# RFID_Reader_v1_0.net
KiCad netlist of a schematic drawn in EAGLE
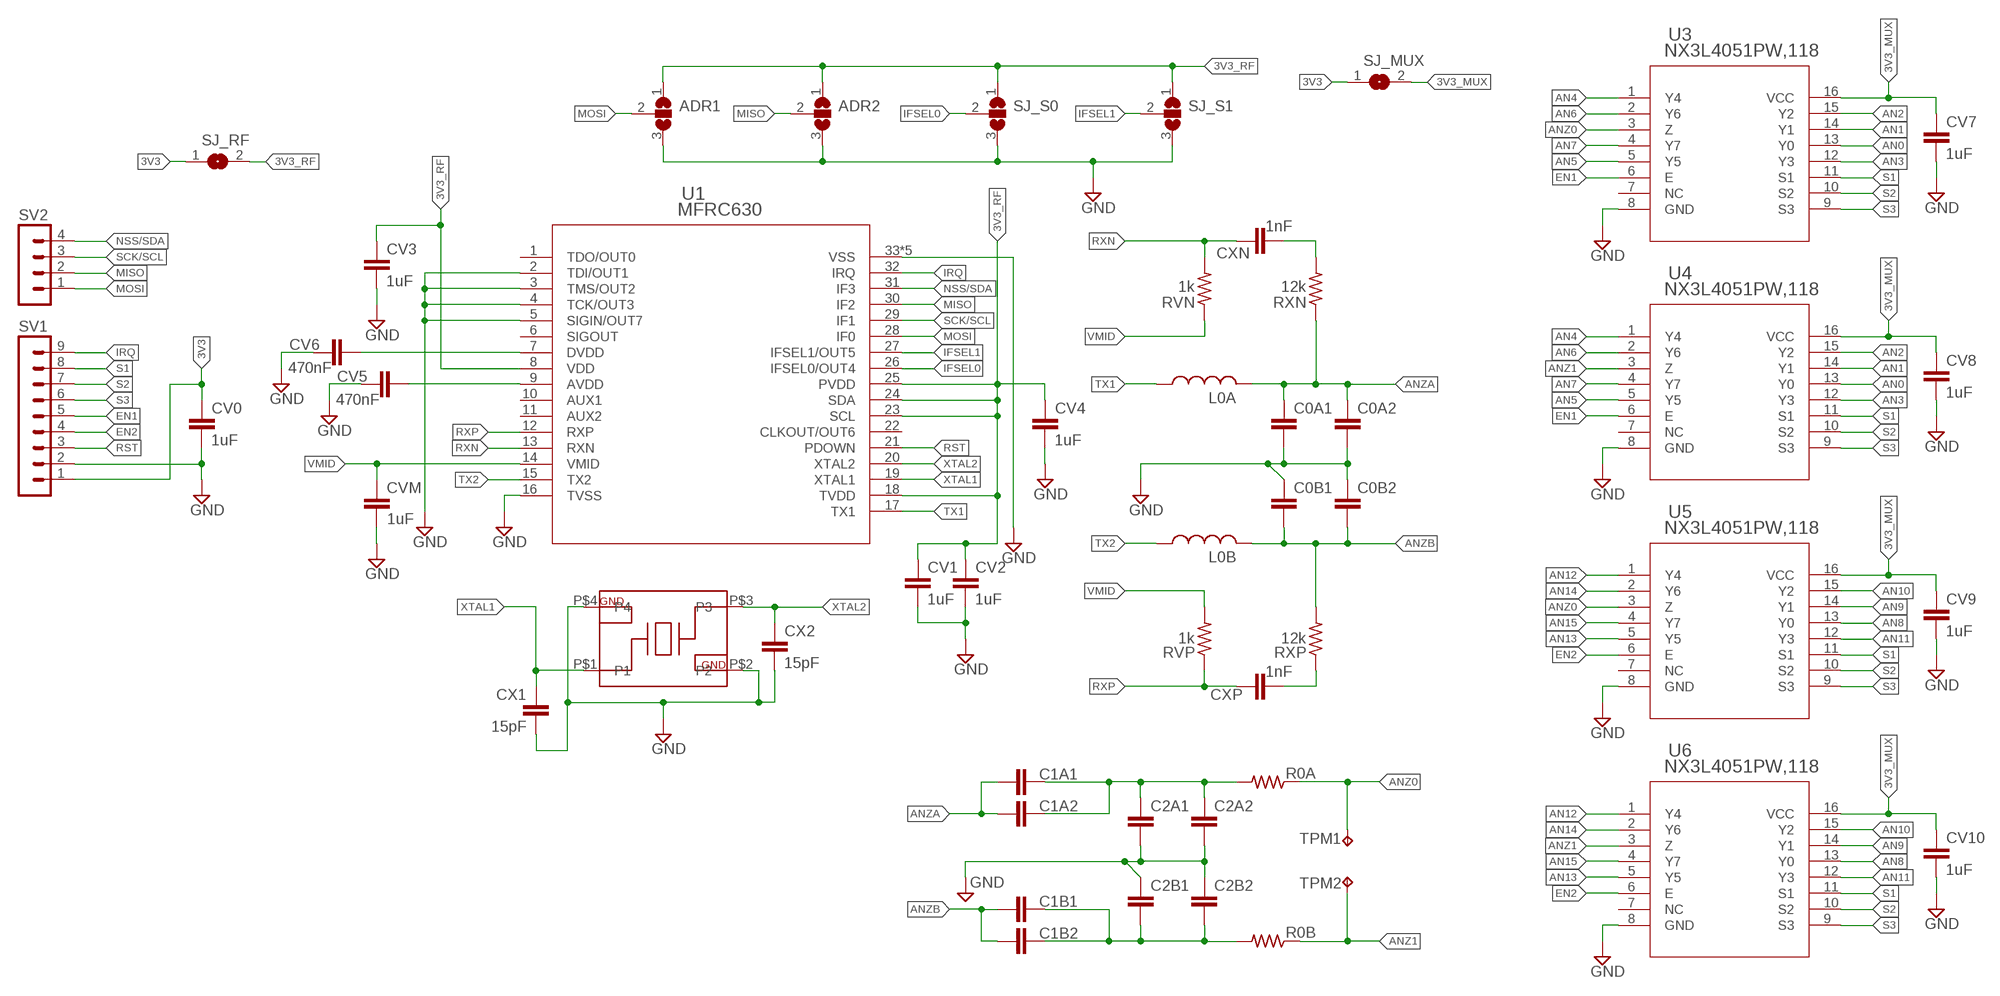
[diagram p0: schematic, sheet 1]

(export (version "E")
  (design (tool "Eeschema 10.0.6"))
  (components
    (comp (ref "ADR1")
      (value "SJ2W")
      (footprint "eagle-import:SJ_2")
      (libsource (lib "eagle-import") (part "SJ2W"))
    )
    (comp (ref "ADR2")
      (value "SJ2W")
      (footprint "eagle-import:SJ_2")
      (libsource (lib "eagle-import") (part "SJ2W"))
    )
    (comp (ref "C0A1")
      (value "C-EUC0805")
      (footprint "eagle-import:C0805")
      (libsource (lib "eagle-import") (part "C-EUC0805"))
    )
    (comp (ref "C0A2")
      (value "C-EUC0805")
      (footprint "eagle-import:C0805")
      (libsource (lib "eagle-import") (part "C-EUC0805"))
    )
    (comp (ref "C0B1")
      (value "C-EUC0805")
      (footprint "eagle-import:C0805")
      (libsource (lib "eagle-import") (part "C-EUC0805"))
    )
    (comp (ref "C0B2")
      (value "C-EUC0805")
      (footprint "eagle-import:C0805")
      (libsource (lib "eagle-import") (part "C-EUC0805"))
    )
    (comp (ref "C1A1")
      (value "C-EUC0805")
      (footprint "eagle-import:C0805")
      (libsource (lib "eagle-import") (part "C-EUC0805"))
    )
    (comp (ref "C1A2")
      (value "C-EUC0805")
      (footprint "eagle-import:C0805")
      (libsource (lib "eagle-import") (part "C-EUC0805"))
    )
    (comp (ref "C1B1")
      (value "C-EUC0805")
      (footprint "eagle-import:C0805")
      (libsource (lib "eagle-import") (part "C-EUC0805"))
    )
    (comp (ref "C1B2")
      (value "C-EUC0805")
      (footprint "eagle-import:C0805")
      (libsource (lib "eagle-import") (part "C-EUC0805"))
    )
    (comp (ref "C2A1")
      (value "C-EUC0805")
      (footprint "eagle-import:C0805")
      (libsource (lib "eagle-import") (part "C-EUC0805"))
    )
    (comp (ref "C2A2")
      (value "C-EUC0805")
      (footprint "eagle-import:C0805")
      (libsource (lib "eagle-import") (part "C-EUC0805"))
    )
    (comp (ref "C2B1")
      (value "C-EUC0805")
      (footprint "eagle-import:C0805")
      (libsource (lib "eagle-import") (part "C-EUC0805"))
    )
    (comp (ref "C2B2")
      (value "C-EUC0805")
      (footprint "eagle-import:C0805")
      (libsource (lib "eagle-import") (part "C-EUC0805"))
    )
    (comp (ref "CV0")
      (value "1uF")
      (footprint "eagle-import:C0402")
      (libsource (lib "eagle-import") (part "C-EUC0402"))
    )
    (comp (ref "CV1")
      (value "1uF")
      (footprint "eagle-import:C0402")
      (libsource (lib "eagle-import") (part "C-EUC0402"))
    )
    (comp (ref "CV2")
      (value "1uF")
      (footprint "eagle-import:C0402")
      (libsource (lib "eagle-import") (part "C-EUC0402"))
    )
    (comp (ref "CV3")
      (value "1uF")
      (footprint "eagle-import:C0402")
      (libsource (lib "eagle-import") (part "C-EUC0402"))
    )
    (comp (ref "CV4")
      (value "1uF")
      (footprint "eagle-import:C0402")
      (libsource (lib "eagle-import") (part "C-EUC0402"))
    )
    (comp (ref "CV5")
      (value "470nF")
      (footprint "eagle-import:C0402")
      (libsource (lib "eagle-import") (part "C-EUC0402"))
    )
    (comp (ref "CV6")
      (value "470nF")
      (footprint "eagle-import:C0402")
      (libsource (lib "eagle-import") (part "C-EUC0402"))
    )
    (comp (ref "CV7")
      (value "1uF")
      (footprint "eagle-import:C0402")
      (libsource (lib "eagle-import") (part "C-EUC0402"))
    )
    (comp (ref "CV8")
      (value "1uF")
      (footprint "eagle-import:C0402")
      (libsource (lib "eagle-import") (part "C-EUC0402"))
    )
    (comp (ref "CV9")
      (value "1uF")
      (footprint "eagle-import:C0402")
      (libsource (lib "eagle-import") (part "C-EUC0402"))
    )
    (comp (ref "CV10")
      (value "1uF")
      (footprint "eagle-import:C0402")
      (libsource (lib "eagle-import") (part "C-EUC0402"))
    )
    (comp (ref "CVM")
      (value "1uF")
      (footprint "eagle-import:C0402")
      (libsource (lib "eagle-import") (part "C-EUC0402"))
    )
    (comp (ref "CX1")
      (value "15pF")
      (footprint "eagle-import:C0402")
      (libsource (lib "eagle-import") (part "C-EUC0402"))
    )
    (comp (ref "CX2")
      (value "15pF")
      (footprint "eagle-import:C0402")
      (libsource (lib "eagle-import") (part "C-EUC0402"))
    )
    (comp (ref "CXN")
      (value "1nF")
      (footprint "eagle-import:C0805")
      (libsource (lib "eagle-import") (part "C-EUC0805"))
    )
    (comp (ref "CXP")
      (value "1nF")
      (footprint "eagle-import:C0805")
      (libsource (lib "eagle-import") (part "C-EUC0805"))
    )
    (comp (ref "L0A")
      (value "L0806")
      (footprint "eagle-import:L0806")
      (libsource (lib "eagle-import") (part "L0806"))
    )
    (comp (ref "L0B")
      (value "L0806")
      (footprint "eagle-import:L0806")
      (libsource (lib "eagle-import") (part "L0806"))
    )
    (comp (ref "R0A")
      (value "R-US_R0805")
      (footprint "eagle-import:R0805")
      (libsource (lib "eagle-import") (part "R-US_R0805"))
    )
    (comp (ref "R0B")
      (value "R-US_R0805")
      (footprint "eagle-import:R0805")
      (libsource (lib "eagle-import") (part "R-US_R0805"))
    )
    (comp (ref "RVN")
      (value "1k")
      (footprint "eagle-import:R0805")
      (libsource (lib "eagle-import") (part "R-US_R0805"))
    )
    (comp (ref "RVP")
      (value "1k")
      (footprint "eagle-import:R0805")
      (libsource (lib "eagle-import") (part "R-US_R0805"))
    )
    (comp (ref "RXN")
      (value "12k")
      (footprint "eagle-import:R0805")
      (libsource (lib "eagle-import") (part "R-US_R0805"))
    )
    (comp (ref "RXP")
      (value "12k")
      (footprint "eagle-import:R0805")
      (libsource (lib "eagle-import") (part "R-US_R0805"))
    )
    (comp (ref "SJ_MUX")
      (value "SJ")
      (footprint "eagle-import:SJ")
      (libsource (lib "eagle-import") (part "SJ"))
    )
    (comp (ref "SJ_RF")
      (value "SJ")
      (footprint "eagle-import:SJ")
      (libsource (lib "eagle-import") (part "SJ"))
    )
    (comp (ref "SJ_S0")
      (value "SJ2W")
      (footprint "eagle-import:SJ_2")
      (libsource (lib "eagle-import") (part "SJ2W"))
    )
    (comp (ref "SJ_S1")
      (value "SJ2W")
      (footprint "eagle-import:SJ_2")
      (libsource (lib "eagle-import") (part "SJ2W"))
    )
    (comp (ref "SV1")
      (value "MA09-1")
      (footprint "eagle-import:MA09-1")
      (libsource (lib "eagle-import") (part "MA09-1"))
    )
    (comp (ref "SV2")
      (value "MA04-1")
      (footprint "eagle-import:MA04-1")
      (libsource (lib "eagle-import") (part "MA04-1"))
    )
    (comp (ref "TPM1")
      (value "TPTP10R")
      (footprint "eagle-import:TP10R")
      (libsource (lib "eagle-import") (part "TPTP10R"))
    )
    (comp (ref "TPM2")
      (value "TPTP10R")
      (footprint "eagle-import:TP10R")
      (libsource (lib "eagle-import") (part "TPTP10R"))
    )
    (comp (ref "U1")
      (value "MFRC630")
      (footprint "eagle-import:HVQFN32_SOT617-1_NXP-M")
      (fields
        (field (name "MANUFACTURER_PART_NUMBER") "MFRC63002HN,118")
        (field (name "COPYRIGHT") "Copyright (C) 2024 Ultra Librarian. All rights reserved.")
      )
      (libsource (lib "eagle-import") (part "MFRC63002HN,118HVQFN32_SOT617-1_NXP-M"))
    )
    (comp (ref "U2")
      (value "E3SB27")
      (footprint "eagle-import:DFN320X250X75-4N")
      (libsource (lib "eagle-import") (part "E3SB27E0X000VEE3SB27E0X000VE"))
    )
    (comp (ref "U3")
      (value "NX3L4051PW,118")
      (footprint "eagle-import:TSSOP16_NXP-M")
      (fields (field (name "COPYRIGHT") "Copyright (C) 2024 Ultra Librarian. All rights reserved."))
      (libsource (lib "eagle-import") (part "NX3L4051PW,118TSSOP16_NXP-M"))
    )
    (comp (ref "U4")
      (value "NX3L4051PW,118")
      (footprint "eagle-import:TSSOP16_NXP-M")
      (fields (field (name "COPYRIGHT") "Copyright (C) 2024 Ultra Librarian. All rights reserved."))
      (libsource (lib "eagle-import") (part "NX3L4051PW,118TSSOP16_NXP-M"))
    )
    (comp (ref "U5")
      (value "NX3L4051PW,118")
      (footprint "eagle-import:TSSOP16_NXP-M")
      (fields (field (name "COPYRIGHT") "Copyright (C) 2024 Ultra Librarian. All rights reserved."))
      (libsource (lib "eagle-import") (part "NX3L4051PW,118TSSOP16_NXP-M"))
    )
    (comp (ref "U6")
      (value "NX3L4051PW,118")
      (footprint "eagle-import:TSSOP16_NXP-M")
      (fields (field (name "COPYRIGHT") "Copyright (C) 2024 Ultra Librarian. All rights reserved."))
      (libsource (lib "eagle-import") (part "NX3L4051PW,118TSSOP16_NXP-M"))
    )
  )
  (nets
    (net (code "1") (name "3V3") (class "Default")
      (node (ref "CV0") (pin "1") (pinfunction "1_1") (pintype "passive"))
      (node (ref "SJ_MUX") (pin "1") (pinfunction "1_1") (pintype "passive"))
      (node (ref "SJ_RF") (pin "1") (pinfunction "1_1") (pintype "passive"))
      (node (ref "SV1") (pin "1") (pinfunction "1_1") (pintype "passive"))
    )
    (net (code "2") (name "3V3_MUX") (class "Default")
      (node (ref "CV10") (pin "1") (pinfunction "1_1") (pintype "passive"))
      (node (ref "CV7") (pin "1") (pinfunction "1_1") (pintype "passive"))
      (node (ref "CV8") (pin "1") (pinfunction "1_1") (pintype "passive"))
      (node (ref "CV9") (pin "1") (pinfunction "1_1") (pintype "passive"))
      (node (ref "SJ_MUX") (pin "2") (pinfunction "2_2") (pintype "passive"))
      (node (ref "U3") (pin "16") (pinfunction "VCC_16") (pintype "power_in"))
      (node (ref "U4") (pin "16") (pinfunction "VCC_16") (pintype "power_in"))
      (node (ref "U5") (pin "16") (pinfunction "VCC_16") (pintype "power_in"))
      (node (ref "U6") (pin "16") (pinfunction "VCC_16") (pintype "power_in"))
    )
    (net (code "3") (name "3V3_RF") (class "Default")
      (node (ref "ADR1") (pin "1") (pinfunction "1_1") (pintype "passive"))
      (node (ref "ADR2") (pin "1") (pinfunction "1_1") (pintype "passive"))
      (node (ref "CV1") (pin "1") (pinfunction "1_1") (pintype "passive"))
      (node (ref "CV2") (pin "1") (pinfunction "1_1") (pintype "passive"))
      (node (ref "CV3") (pin "1") (pinfunction "1_1") (pintype "passive"))
      (node (ref "CV4") (pin "1") (pinfunction "1_1") (pintype "passive"))
      (node (ref "SJ_RF") (pin "2") (pinfunction "2_2") (pintype "passive"))
      (node (ref "SJ_S0") (pin "1") (pinfunction "1_1") (pintype "passive"))
      (node (ref "SJ_S1") (pin "1") (pinfunction "1_1") (pintype "passive"))
      (node (ref "U1") (pin "18") (pinfunction "TVDD_18") (pintype "power_in"))
      (node (ref "U1") (pin "23") (pinfunction "SCL_23") (pintype "output"))
      (node (ref "U1") (pin "24") (pinfunction "SDA_24") (pintype "bidirectional"))
      (node (ref "U1") (pin "25") (pinfunction "PVDD_25") (pintype "power_in"))
      (node (ref "U1") (pin "8") (pinfunction "VDD_8") (pintype "power_in"))
    )
    (net (code "4") (name "AN0") (class "Default")
      (node (ref "U3") (pin "13") (pinfunction "Y0_13") (pintype "bidirectional"))
      (node (ref "U4") (pin "13") (pinfunction "Y0_13") (pintype "bidirectional"))
    )
    (net (code "5") (name "AN1") (class "Default")
      (node (ref "U3") (pin "14") (pinfunction "Y1_14") (pintype "bidirectional"))
      (node (ref "U4") (pin "14") (pinfunction "Y1_14") (pintype "bidirectional"))
    )
    (net (code "6") (name "AN2") (class "Default")
      (node (ref "U3") (pin "15") (pinfunction "Y2_15") (pintype "bidirectional"))
      (node (ref "U4") (pin "15") (pinfunction "Y2_15") (pintype "bidirectional"))
    )
    (net (code "7") (name "AN3") (class "Default")
      (node (ref "U3") (pin "12") (pinfunction "Y3_12") (pintype "bidirectional"))
      (node (ref "U4") (pin "12") (pinfunction "Y3_12") (pintype "bidirectional"))
    )
    (net (code "8") (name "AN4") (class "Default")
      (node (ref "U3") (pin "1") (pinfunction "Y4_1") (pintype "bidirectional"))
      (node (ref "U4") (pin "1") (pinfunction "Y4_1") (pintype "bidirectional"))
    )
    (net (code "9") (name "AN5") (class "Default")
      (node (ref "U3") (pin "5") (pinfunction "Y5_5") (pintype "bidirectional"))
      (node (ref "U4") (pin "5") (pinfunction "Y5_5") (pintype "bidirectional"))
    )
    (net (code "10") (name "AN6") (class "Default")
      (node (ref "U3") (pin "2") (pinfunction "Y6_2") (pintype "bidirectional"))
      (node (ref "U4") (pin "2") (pinfunction "Y6_2") (pintype "bidirectional"))
    )
    (net (code "11") (name "AN7") (class "Default")
      (node (ref "U3") (pin "4") (pinfunction "Y7_4") (pintype "bidirectional"))
      (node (ref "U4") (pin "4") (pinfunction "Y7_4") (pintype "bidirectional"))
    )
    (net (code "12") (name "AN8") (class "Default")
      (node (ref "U5") (pin "13") (pinfunction "Y0_13") (pintype "bidirectional"))
      (node (ref "U6") (pin "13") (pinfunction "Y0_13") (pintype "bidirectional"))
    )
    (net (code "13") (name "AN9") (class "Default")
      (node (ref "U5") (pin "14") (pinfunction "Y1_14") (pintype "bidirectional"))
      (node (ref "U6") (pin "14") (pinfunction "Y1_14") (pintype "bidirectional"))
    )
    (net (code "14") (name "AN10") (class "Default")
      (node (ref "U5") (pin "15") (pinfunction "Y2_15") (pintype "bidirectional"))
      (node (ref "U6") (pin "15") (pinfunction "Y2_15") (pintype "bidirectional"))
    )
    (net (code "15") (name "AN11") (class "Default")
      (node (ref "U5") (pin "12") (pinfunction "Y3_12") (pintype "bidirectional"))
      (node (ref "U6") (pin "12") (pinfunction "Y3_12") (pintype "bidirectional"))
    )
    (net (code "16") (name "AN12") (class "Default")
      (node (ref "U5") (pin "1") (pinfunction "Y4_1") (pintype "bidirectional"))
      (node (ref "U6") (pin "1") (pinfunction "Y4_1") (pintype "bidirectional"))
    )
    (net (code "17") (name "AN13") (class "Default")
      (node (ref "U5") (pin "5") (pinfunction "Y5_5") (pintype "bidirectional"))
      (node (ref "U6") (pin "5") (pinfunction "Y5_5") (pintype "bidirectional"))
    )
    (net (code "18") (name "AN14") (class "Default")
      (node (ref "U5") (pin "2") (pinfunction "Y6_2") (pintype "bidirectional"))
      (node (ref "U6") (pin "2") (pinfunction "Y6_2") (pintype "bidirectional"))
    )
    (net (code "19") (name "AN15") (class "Default")
      (node (ref "U5") (pin "4") (pinfunction "Y7_4") (pintype "bidirectional"))
      (node (ref "U6") (pin "4") (pinfunction "Y7_4") (pintype "bidirectional"))
    )
    (net (code "20") (name "ANZ0") (class "Default")
      (node (ref "R0A") (pin "1") (pinfunction "1_1") (pintype "passive"))
      (node (ref "TPM1") (pin "TP") (pinfunction "TP_TP") (pintype "input"))
      (node (ref "U3") (pin "3") (pinfunction "Z_3") (pintype "bidirectional"))
      (node (ref "U5") (pin "3") (pinfunction "Z_3") (pintype "bidirectional"))
    )
    (net (code "21") (name "ANZ1") (class "Default")
      (node (ref "R0B") (pin "1") (pinfunction "1_1") (pintype "passive"))
      (node (ref "TPM2") (pin "TP") (pinfunction "TP_TP") (pintype "input"))
      (node (ref "U4") (pin "3") (pinfunction "Z_3") (pintype "bidirectional"))
      (node (ref "U6") (pin "3") (pinfunction "Z_3") (pintype "bidirectional"))
    )
    (net (code "22") (name "ANZA") (class "Default")
      (node (ref "C0A1") (pin "1") (pinfunction "1_1") (pintype "passive"))
      (node (ref "C0A2") (pin "1") (pinfunction "1_1") (pintype "passive"))
      (node (ref "C1A1") (pin "2") (pinfunction "2_2") (pintype "passive"))
      (node (ref "C1A2") (pin "2") (pinfunction "2_2") (pintype "passive"))
      (node (ref "L0A") (pin "2") (pinfunction "2_2") (pintype "passive"))
      (node (ref "RXN") (pin "1") (pinfunction "1_1") (pintype "passive"))
    )
    (net (code "23") (name "ANZB") (class "Default")
      (node (ref "C0B1") (pin "2") (pinfunction "2_2") (pintype "passive"))
      (node (ref "C0B2") (pin "2") (pinfunction "2_2") (pintype "passive"))
      (node (ref "C1B1") (pin "2") (pinfunction "2_2") (pintype "passive"))
      (node (ref "C1B2") (pin "2") (pinfunction "2_2") (pintype "passive"))
      (node (ref "L0B") (pin "2") (pinfunction "2_2") (pintype "passive"))
      (node (ref "RXP") (pin "2") (pinfunction "2_2") (pintype "passive"))
    )
    (net (code "24") (name "EN1") (class "Default")
      (node (ref "SV1") (pin "5") (pinfunction "5_5") (pintype "passive"))
      (node (ref "U3") (pin "6") (pinfunction "E_6") (pintype "input"))
      (node (ref "U4") (pin "6") (pinfunction "E_6") (pintype "input"))
    )
    (net (code "25") (name "EN2") (class "Default")
      (node (ref "SV1") (pin "4") (pinfunction "4_4") (pintype "passive"))
      (node (ref "U5") (pin "6") (pinfunction "E_6") (pintype "input"))
      (node (ref "U6") (pin "6") (pinfunction "E_6") (pintype "input"))
    )
    (net (code "26") (name "GND") (class "Default")
      (node (ref "ADR1") (pin "3") (pinfunction "3_3") (pintype "passive"))
      (node (ref "ADR2") (pin "3") (pinfunction "3_3") (pintype "passive"))
      (node (ref "C0A1") (pin "2") (pinfunction "2_2") (pintype "passive"))
      (node (ref "C0A2") (pin "2") (pinfunction "2_2") (pintype "passive"))
      (node (ref "C0B1") (pin "1") (pinfunction "1_1") (pintype "passive"))
      (node (ref "C0B2") (pin "1") (pinfunction "1_1") (pintype "passive"))
      (node (ref "C2A1") (pin "2") (pinfunction "2_2") (pintype "passive"))
      (node (ref "C2A2") (pin "2") (pinfunction "2_2") (pintype "passive"))
      (node (ref "C2B1") (pin "1") (pinfunction "1_1") (pintype "passive"))
      (node (ref "C2B2") (pin "1") (pinfunction "1_1") (pintype "passive"))
      (node (ref "CV0") (pin "2") (pinfunction "2_2") (pintype "passive"))
      (node (ref "CV1") (pin "2") (pinfunction "2_2") (pintype "passive"))
      (node (ref "CV10") (pin "2") (pinfunction "2_2") (pintype "passive"))
      (node (ref "CV2") (pin "2") (pinfunction "2_2") (pintype "passive"))
      (node (ref "CV3") (pin "2") (pinfunction "2_2") (pintype "passive"))
      (node (ref "CV4") (pin "2") (pinfunction "2_2") (pintype "passive"))
      (node (ref "CV5") (pin "2") (pinfunction "2_2") (pintype "passive"))
      (node (ref "CV6") (pin "2") (pinfunction "2_2") (pintype "passive"))
      (node (ref "CV7") (pin "2") (pinfunction "2_2") (pintype "passive"))
      (node (ref "CV8") (pin "2") (pinfunction "2_2") (pintype "passive"))
      (node (ref "CV9") (pin "2") (pinfunction "2_2") (pintype "passive"))
      (node (ref "CVM") (pin "2") (pinfunction "2_2") (pintype "passive"))
      (node (ref "CX1") (pin "2") (pinfunction "2_2") (pintype "passive"))
      (node (ref "CX2") (pin "2") (pinfunction "2_2") (pintype "passive"))
      (node (ref "SJ_S0") (pin "3") (pinfunction "3_3") (pintype "passive"))
      (node (ref "SJ_S1") (pin "3") (pinfunction "3_3") (pintype "passive"))
      (node (ref "SV1") (pin "2") (pinfunction "2_2") (pintype "passive"))
      (node (ref "U1") (pin "16") (pinfunction "TVSS_16") (pintype "passive"))
      (node (ref "U1") (pin "2") (pinfunction "TDI/OUT1_2") (pintype "input"))
      (node (ref "U1") (pin "3") (pinfunction "TMS/OUT2_3") (pintype "input"))
      (node (ref "U1") (pin "33") (pinfunction "VSS_33") (pintype "passive"))
      (node (ref "U1") (pin "4") (pinfunction "TCK/OUT3_4") (pintype "input"))
      (node (ref "U1") (pin "5") (pinfunction "SIGIN/OUT7_5") (pintype "bidirectional"))
      (node (ref "U1") (pin "P$1") (pinfunction "VSS_P$1") (pintype "passive"))
      (node (ref "U1") (pin "P$2") (pinfunction "VSS_P$2") (pintype "passive"))
      (node (ref "U1") (pin "P$3") (pinfunction "VSS_P$3") (pintype "passive"))
      (node (ref "U1") (pin "P$4") (pinfunction "VSS_P$4") (pintype "passive"))
      (node (ref "U2") (pin "P$2") (pinfunction "P2_P$2") (pintype "input"))
      (node (ref "U2") (pin "P$4") (pinfunction "P4_P$4") (pintype "input"))
      (node (ref "U3") (pin "8") (pinfunction "GND_8") (pintype "passive"))
      (node (ref "U4") (pin "8") (pinfunction "GND_8") (pintype "passive"))
      (node (ref "U5") (pin "8") (pinfunction "GND_8") (pintype "passive"))
      (node (ref "U6") (pin "8") (pinfunction "GND_8") (pintype "passive"))
    )
    (net (code "27") (name "IFSEL0") (class "Default")
      (node (ref "SJ_S0") (pin "2") (pinfunction "2_2") (pintype "passive"))
      (node (ref "U1") (pin "26") (pinfunction "IFSEL0/OUT4_26") (pintype "input"))
    )
    (net (code "28") (name "IFSEL1") (class "Default")
      (node (ref "SJ_S1") (pin "2") (pinfunction "2_2") (pintype "passive"))
      (node (ref "U1") (pin "27") (pinfunction "IFSEL1/OUT5_27") (pintype "input"))
    )
    (net (code "29") (name "IRQ") (class "Default")
      (node (ref "SV1") (pin "9") (pinfunction "9_9") (pintype "passive"))
      (node (ref "U1") (pin "32") (pinfunction "IRQ_32") (pintype "output"))
    )
    (net (code "30") (name "MISO") (class "Default")
      (node (ref "ADR2") (pin "2") (pinfunction "2_2") (pintype "passive"))
      (node (ref "SV2") (pin "2") (pinfunction "2_2") (pintype "passive"))
      (node (ref "U1") (pin "30") (pinfunction "IF2_30") (pintype "bidirectional"))
    )
    (net (code "31") (name "MOSI") (class "Default")
      (node (ref "ADR1") (pin "2") (pinfunction "2_2") (pintype "passive"))
      (node (ref "SV2") (pin "1") (pinfunction "1_1") (pintype "passive"))
      (node (ref "U1") (pin "28") (pinfunction "IF0_28") (pintype "bidirectional"))
    )
    (net (code "32") (name "NSS{slash}SDA") (class "Default")
      (node (ref "SV2") (pin "4") (pinfunction "4_4") (pintype "passive"))
      (node (ref "U1") (pin "31") (pinfunction "IF3_31") (pintype "bidirectional"))
    )
    (net (code "33") (name "Net-(C1A1-Pad1)") (class "Default")
      (node (ref "C1A1") (pin "1") (pinfunction "1_1") (pintype "passive"))
      (node (ref "C1A2") (pin "1") (pinfunction "1_1") (pintype "passive"))
      (node (ref "C2A1") (pin "1") (pinfunction "1_1") (pintype "passive"))
      (node (ref "C2A2") (pin "1") (pinfunction "1_1") (pintype "passive"))
      (node (ref "R0A") (pin "2") (pinfunction "2_2") (pintype "passive"))
    )
    (net (code "34") (name "Net-(C1B1-Pad1)") (class "Default")
      (node (ref "C1B1") (pin "1") (pinfunction "1_1") (pintype "passive"))
      (node (ref "C1B2") (pin "1") (pinfunction "1_1") (pintype "passive"))
      (node (ref "C2B1") (pin "2") (pinfunction "2_2") (pintype "passive"))
      (node (ref "C2B2") (pin "2") (pinfunction "2_2") (pintype "passive"))
      (node (ref "R0B") (pin "2") (pinfunction "2_2") (pintype "passive"))
    )
    (net (code "35") (name "Net-(CXN-Pad2)") (class "Default")
      (node (ref "CXN") (pin "2") (pinfunction "2_2") (pintype "passive"))
      (node (ref "RXN") (pin "2") (pinfunction "2_2") (pintype "passive"))
    )
    (net (code "36") (name "Net-(CXP-Pad2)") (class "Default")
      (node (ref "CXP") (pin "2") (pinfunction "2_2") (pintype "passive"))
      (node (ref "RXP") (pin "1") (pinfunction "1_1") (pintype "passive"))
    )
    (net (code "37") (name "Net-(U1-AVDD)") (class "Default")
      (node (ref "CV5") (pin "1") (pinfunction "1_1") (pintype "passive"))
      (node (ref "U1") (pin "9") (pinfunction "AVDD_9") (pintype "power_in"))
    )
    (net (code "38") (name "Net-(U1-DVDD)") (class "Default")
      (node (ref "CV6") (pin "1") (pinfunction "1_1") (pintype "passive"))
      (node (ref "U1") (pin "7") (pinfunction "DVDD_7") (pintype "power_in"))
    )
    (net (code "39") (name "RST") (class "Default")
      (node (ref "SV1") (pin "3") (pinfunction "3_3") (pintype "passive"))
      (node (ref "U1") (pin "21") (pinfunction "PDOWN_21") (pintype "input"))
    )
    (net (code "40") (name "RXN") (class "Default")
      (node (ref "CXN") (pin "1") (pinfunction "1_1") (pintype "passive"))
      (node (ref "RVN") (pin "2") (pinfunction "2_2") (pintype "passive"))
      (node (ref "U1") (pin "13") (pinfunction "RXN_13") (pintype "input"))
    )
    (net (code "41") (name "RXP") (class "Default")
      (node (ref "CXP") (pin "1") (pinfunction "1_1") (pintype "passive"))
      (node (ref "RVP") (pin "1") (pinfunction "1_1") (pintype "passive"))
      (node (ref "U1") (pin "12") (pinfunction "RXP_12") (pintype "input"))
    )
    (net (code "42") (name "S1") (class "Default")
      (node (ref "SV1") (pin "8") (pinfunction "8_8") (pintype "passive"))
      (node (ref "U3") (pin "11") (pinfunction "S1_11") (pintype "input"))
      (node (ref "U4") (pin "11") (pinfunction "S1_11") (pintype "input"))
      (node (ref "U5") (pin "11") (pinfunction "S1_11") (pintype "input"))
      (node (ref "U6") (pin "11") (pinfunction "S1_11") (pintype "input"))
    )
    (net (code "43") (name "S2") (class "Default")
      (node (ref "SV1") (pin "7") (pinfunction "7_7") (pintype "passive"))
      (node (ref "U3") (pin "10") (pinfunction "S2_10") (pintype "input"))
      (node (ref "U4") (pin "10") (pinfunction "S2_10") (pintype "input"))
      (node (ref "U5") (pin "10") (pinfunction "S2_10") (pintype "input"))
      (node (ref "U6") (pin "10") (pinfunction "S2_10") (pintype "input"))
    )
    (net (code "44") (name "S3") (class "Default")
      (node (ref "SV1") (pin "6") (pinfunction "6_6") (pintype "passive"))
      (node (ref "U3") (pin "9") (pinfunction "S3_9") (pintype "input"))
      (node (ref "U4") (pin "9") (pinfunction "S3_9") (pintype "input"))
      (node (ref "U5") (pin "9") (pinfunction "S3_9") (pintype "input"))
      (node (ref "U6") (pin "9") (pinfunction "S3_9") (pintype "input"))
    )
    (net (code "45") (name "SCK{slash}SCL") (class "Default")
      (node (ref "SV2") (pin "3") (pinfunction "3_3") (pintype "passive"))
      (node (ref "U1") (pin "29") (pinfunction "IF1_29") (pintype "bidirectional"))
    )
    (net (code "46") (name "TX1") (class "Default")
      (node (ref "L0A") (pin "1") (pinfunction "1_1") (pintype "passive"))
      (node (ref "U1") (pin "17") (pinfunction "TX1_17") (pintype "output"))
    )
    (net (code "47") (name "TX2") (class "Default")
      (node (ref "L0B") (pin "1") (pinfunction "1_1") (pintype "passive"))
      (node (ref "U1") (pin "15") (pinfunction "TX2_15") (pintype "output"))
    )
    (net (code "48") (name "VMID") (class "Default")
      (node (ref "CVM") (pin "1") (pinfunction "1_1") (pintype "passive"))
      (node (ref "RVN") (pin "1") (pinfunction "1_1") (pintype "passive"))
      (node (ref "RVP") (pin "2") (pinfunction "2_2") (pintype "passive"))
      (node (ref "U1") (pin "14") (pinfunction "VMID_14") (pintype "power_in"))
    )
    (net (code "49") (name "XTAL1") (class "Default")
      (node (ref "CX1") (pin "1") (pinfunction "1_1") (pintype "passive"))
      (node (ref "U1") (pin "19") (pinfunction "XTAL1_19") (pintype "input"))
      (node (ref "U2") (pin "P$1") (pinfunction "P1_P$1") (pintype "bidirectional"))
    )
    (net (code "50") (name "XTAL2") (class "Default")
      (node (ref "CX2") (pin "1") (pinfunction "1_1") (pintype "passive"))
      (node (ref "U1") (pin "20") (pinfunction "XTAL2_20") (pintype "output"))
      (node (ref "U2") (pin "P$3") (pinfunction "P3_P$3") (pintype "bidirectional"))
    )
    (net (code "51") (name "unconnected-(U1-AUX1-Pad10)") (class "Default")
      (node (ref "U1") (pin "10") (pinfunction "AUX1_10") (pintype "output"))
    )
    (net (code "52") (name "unconnected-(U1-AUX2-Pad11)") (class "Default")
      (node (ref "U1") (pin "11") (pinfunction "AUX2_11") (pintype "output"))
    )
    (net (code "53") (name "unconnected-(U1-CLKOUT{slash}OUT6-Pad22)") (class "Default")
      (node (ref "U1") (pin "22") (pinfunction "CLKOUT/OUT6_22") (pintype "output"))
    )
    (net (code "54") (name "unconnected-(U1-SIGOUT-Pad6)") (class "Default")
      (node (ref "U1") (pin "6") (pinfunction "SIGOUT_6") (pintype "output"))
    )
    (net (code "55") (name "unconnected-(U1-TDO{slash}OUT0-Pad1)") (class "Default")
      (node (ref "U1") (pin "1") (pinfunction "TDO/OUT0_1") (pintype "output"))
    )
    (net (code "56") (name "unconnected-(U3-NC-Pad7)") (class "Default")
      (node (ref "U3") (pin "7") (pinfunction "NC_7") (pintype "no_connect"))
    )
    (net (code "57") (name "unconnected-(U4-NC-Pad7)") (class "Default")
      (node (ref "U4") (pin "7") (pinfunction "NC_7") (pintype "no_connect"))
    )
    (net (code "58") (name "unconnected-(U5-NC-Pad7)") (class "Default")
      (node (ref "U5") (pin "7") (pinfunction "NC_7") (pintype "no_connect"))
    )
    (net (code "59") (name "unconnected-(U6-NC-Pad7)") (class "Default")
      (node (ref "U6") (pin "7") (pinfunction "NC_7") (pintype "no_connect"))
    )
  )
)
